# Motor.net
KiCad netlist of a schematic drawn in Altium Designer
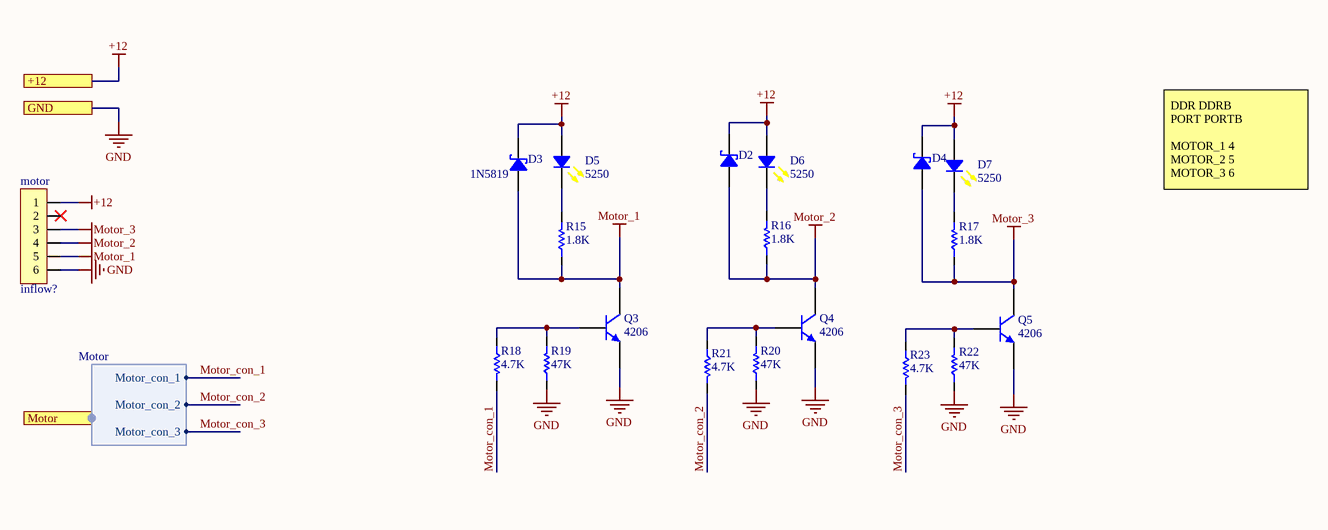
[diagram p0: Motor.SchDoc]

(export (version "E")
  (design (tool "Eeschema 10.0.6"))
  (components
    (comp (ref "D2")
      (value "1N5819")
      (footprint "430X270D")
      (description "Schottky Rectifiers")
      (fields (field (name "VALIDATION") "Valid"))
      (libsource (lib "aKaReZa") (part "Semi_Diod_Sch_1N5819_SMD"))
    )
    (comp (ref "D3")
      (value "1N5819")
      (footprint "430X270D")
      (description "Schottky Rectifiers")
      (fields (field (name "VALIDATION") "Valid"))
      (libsource (lib "aKaReZa") (part "Semi_Diod_Sch_1N5819_SMD"))
    )
    (comp (ref "D4")
      (value "1N5819")
      (footprint "430X270D")
      (description "Schottky Rectifiers")
      (fields (field (name "VALIDATION") "Valid"))
      (libsource (lib "aKaReZa") (part "Semi_Diod_Sch_1N5819_SMD"))
    )
    (comp (ref "D5")
      (value "Yellow, 1206")
      (footprint "LED 1206/3216 YELLOW")
      (description "LED")
      (fields (field (name "INFLOW") "5250") (field (name "VALIDATION") "Valid"))
      (libsource (lib "aKaReZa") (part "Semi_LED_Yellow_1206"))
    )
    (comp (ref "D6")
      (value "Yellow, 1206")
      (footprint "LED 1206/3216 YELLOW")
      (description "LED")
      (fields (field (name "INFLOW") "5250") (field (name "VALIDATION") "Valid"))
      (libsource (lib "aKaReZa") (part "Semi_LED_Yellow_1206"))
    )
    (comp (ref "D7")
      (value "Yellow, 1206")
      (footprint "LED 1206/3216 YELLOW")
      (description "LED")
      (fields (field (name "INFLOW") "5250") (field (name "VALIDATION") "Valid"))
      (libsource (lib "aKaReZa") (part "Semi_LED_Yellow_1206"))
    )
    (comp (ref "motor")
      (value "6'Pin")
      (footprint "MOLEX KK 0022272061")
      (description "Signal Connector 6'Pin")
      (fields (field (name "INFLOW") "inflow?") (field (name "VALIDATION") "Valid"))
      (libsource (lib "aKaReZa") (part "Con_Signal_6"))
    )
    (comp (ref "Q3")
      (value "NPN")
      (footprint "TO-220 AB")
      (description "NPN Power transistor")
      (fields (field (name "INFLOW") "4206") (field (name "VALIDATION") "NT"))
      (libsource (lib "aKaReZa") (part "Semi_BJT_TIP41C"))
    )
    (comp (ref "Q4")
      (value "NPN")
      (footprint "TO-220 AB")
      (description "NPN Power transistor")
      (fields (field (name "INFLOW") "4206") (field (name "VALIDATION") "NT"))
      (libsource (lib "aKaReZa") (part "Semi_BJT_TIP41C"))
    )
    (comp (ref "Q5")
      (value "NPN")
      (footprint "TO-220 AB")
      (description "NPN Power transistor")
      (fields (field (name "INFLOW") "4206") (field (name "VALIDATION") "NT"))
      (libsource (lib "aKaReZa") (part "Semi_BJT_TIP41C"))
    )
    (comp (ref "R15")
      (value "1.8K")
      (footprint "RES 1206 (3216X08L)")
      (description "Resistor")
      (fields (field (name "VALIDATION") "Valid"))
      (libsource (lib "aKaReZa") (part "Res_SMD_1206"))
    )
    (comp (ref "R16")
      (value "1.8K")
      (footprint "RES 1206 (3216X08L)")
      (description "Resistor")
      (fields (field (name "VALIDATION") "Valid"))
      (libsource (lib "aKaReZa") (part "Res_SMD_1206"))
    )
    (comp (ref "R17")
      (value "1.8K")
      (footprint "RES 1206 (3216X08L)")
      (description "Resistor")
      (fields (field (name "VALIDATION") "Valid"))
      (libsource (lib "aKaReZa") (part "Res_SMD_1206"))
    )
    (comp (ref "R18")
      (value "4.7K")
      (footprint "RES 1206 (3216X08L)")
      (description "Resistor")
      (fields (field (name "VALIDATION") "Valid"))
      (libsource (lib "aKaReZa") (part "Res_SMD_1206"))
    )
    (comp (ref "R19")
      (value "47K")
      (footprint "RES 1206 (3216X08L)")
      (description "Resistor")
      (fields (field (name "VALIDATION") "Valid"))
      (libsource (lib "aKaReZa") (part "Res_SMD_1206"))
    )
    (comp (ref "R20")
      (value "47K")
      (footprint "RES 1206 (3216X08L)")
      (description "Resistor")
      (fields (field (name "VALIDATION") "Valid"))
      (libsource (lib "aKaReZa") (part "Res_SMD_1206"))
    )
    (comp (ref "R21")
      (value "4.7K")
      (footprint "RES 1206 (3216X08L)")
      (description "Resistor")
      (fields (field (name "VALIDATION") "Valid"))
      (libsource (lib "aKaReZa") (part "Res_SMD_1206"))
    )
    (comp (ref "R22")
      (value "47K")
      (footprint "RES 1206 (3216X08L)")
      (description "Resistor")
      (fields (field (name "VALIDATION") "Valid"))
      (libsource (lib "aKaReZa") (part "Res_SMD_1206"))
    )
    (comp (ref "R23")
      (value "4.7K")
      (footprint "RES 1206 (3216X08L)")
      (description "Resistor")
      (fields (field (name "VALIDATION") "Valid"))
      (libsource (lib "aKaReZa") (part "Res_SMD_1206"))
    )
  )
  (nets
    (net (code "2") (name "+12") (class "Default")
      (node (ref "D2") (pin "2") (pinfunction "2_2") (pintype "passive"))
      (node (ref "D3") (pin "2") (pinfunction "2_2") (pintype "passive"))
      (node (ref "D4") (pin "2") (pinfunction "2_2") (pintype "passive"))
      (node (ref "D5") (pin "1") (pinfunction "1_1") (pintype "passive"))
      (node (ref "D6") (pin "1") (pinfunction "1_1") (pintype "passive"))
      (node (ref "D7") (pin "1") (pinfunction "1_1") (pintype "passive"))
      (node (ref "motor") (pin "1") (pinfunction "1_1") (pintype "passive"))
    )
    (net (code "4") (name "/Motor_con_1") (class "Default")
      (node (ref "R18") (pin "2") (pinfunction "2_2") (pintype "passive"))
    )
    (net (code "5") (name "/Motor_con_2") (class "Default")
      (node (ref "R21") (pin "2") (pinfunction "2_2") (pintype "passive"))
    )
    (net (code "6") (name "/Motor_con_3") (class "Default")
      (node (ref "R23") (pin "2") (pinfunction "2_2") (pintype "passive"))
    )
    (net (code "8") (name "GND") (class "Default")
      (node (ref "Q3") (pin "3") (pinfunction "E_3") (pintype "passive"))
      (node (ref "Q4") (pin "3") (pinfunction "E_3") (pintype "passive"))
      (node (ref "Q5") (pin "3") (pinfunction "E_3") (pintype "passive"))
      (node (ref "R19") (pin "1") (pinfunction "1_1") (pintype "passive"))
      (node (ref "R20") (pin "1") (pinfunction "1_1") (pintype "passive"))
      (node (ref "R22") (pin "1") (pinfunction "1_1") (pintype "passive"))
      (node (ref "motor") (pin "6") (pinfunction "6_6") (pintype "passive"))
    )
    (net (code "9") (name "Motor_1") (class "Default")
      (node (ref "D3") (pin "1") (pinfunction "1_1") (pintype "passive"))
      (node (ref "Q3") (pin "2") (pinfunction "C_2") (pintype "passive"))
      (node (ref "R15") (pin "1") (pinfunction "1_1") (pintype "passive"))
      (node (ref "motor") (pin "5") (pinfunction "5_5") (pintype "passive"))
    )
    (net (code "10") (name "Motor_2") (class "Default")
      (node (ref "D2") (pin "1") (pinfunction "1_1") (pintype "passive"))
      (node (ref "Q4") (pin "2") (pinfunction "C_2") (pintype "passive"))
      (node (ref "R16") (pin "1") (pinfunction "1_1") (pintype "passive"))
      (node (ref "motor") (pin "4") (pinfunction "4_4") (pintype "passive"))
    )
    (net (code "11") (name "Motor_3") (class "Default")
      (node (ref "D4") (pin "1") (pinfunction "1_1") (pintype "passive"))
      (node (ref "Q5") (pin "2") (pinfunction "C_2") (pintype "passive"))
      (node (ref "R17") (pin "1") (pinfunction "1_1") (pintype "passive"))
      (node (ref "motor") (pin "3") (pinfunction "3_3") (pintype "passive"))
    )
    (net (code "12") (name "Net-(D5-Pad2)") (class "Default")
      (node (ref "D5") (pin "2") (pinfunction "2_2") (pintype "passive"))
      (node (ref "R15") (pin "2") (pinfunction "2_2") (pintype "passive"))
    )
    (net (code "13") (name "Net-(D6-Pad2)") (class "Default")
      (node (ref "D6") (pin "2") (pinfunction "2_2") (pintype "passive"))
      (node (ref "R16") (pin "2") (pinfunction "2_2") (pintype "passive"))
    )
    (net (code "14") (name "Net-(D7-Pad2)") (class "Default")
      (node (ref "D7") (pin "2") (pinfunction "2_2") (pintype "passive"))
      (node (ref "R17") (pin "2") (pinfunction "2_2") (pintype "passive"))
    )
    (net (code "15") (name "Net-(Q3-B)") (class "Default")
      (node (ref "Q3") (pin "1") (pinfunction "B_1") (pintype "passive"))
      (node (ref "R18") (pin "1") (pinfunction "1_1") (pintype "passive"))
      (node (ref "R19") (pin "2") (pinfunction "2_2") (pintype "passive"))
    )
    (net (code "16") (name "Net-(Q4-B)") (class "Default")
      (node (ref "Q4") (pin "1") (pinfunction "B_1") (pintype "passive"))
      (node (ref "R20") (pin "2") (pinfunction "2_2") (pintype "passive"))
      (node (ref "R21") (pin "1") (pinfunction "1_1") (pintype "passive"))
    )
    (net (code "17") (name "Net-(Q5-B)") (class "Default")
      (node (ref "Q5") (pin "1") (pinfunction "B_1") (pintype "passive"))
      (node (ref "R22") (pin "2") (pinfunction "2_2") (pintype "passive"))
      (node (ref "R23") (pin "1") (pinfunction "1_1") (pintype "passive"))
    )
    (net (code "18") (name "unconnected-(motor-Pad2)") (class "Default")
      (node (ref "motor") (pin "2") (pinfunction "2_2") (pintype "passive+no_connect"))
    )
  )
)
